# 1_0_-_First_design.net
KiCad netlist of a schematic drawn in EAGLE
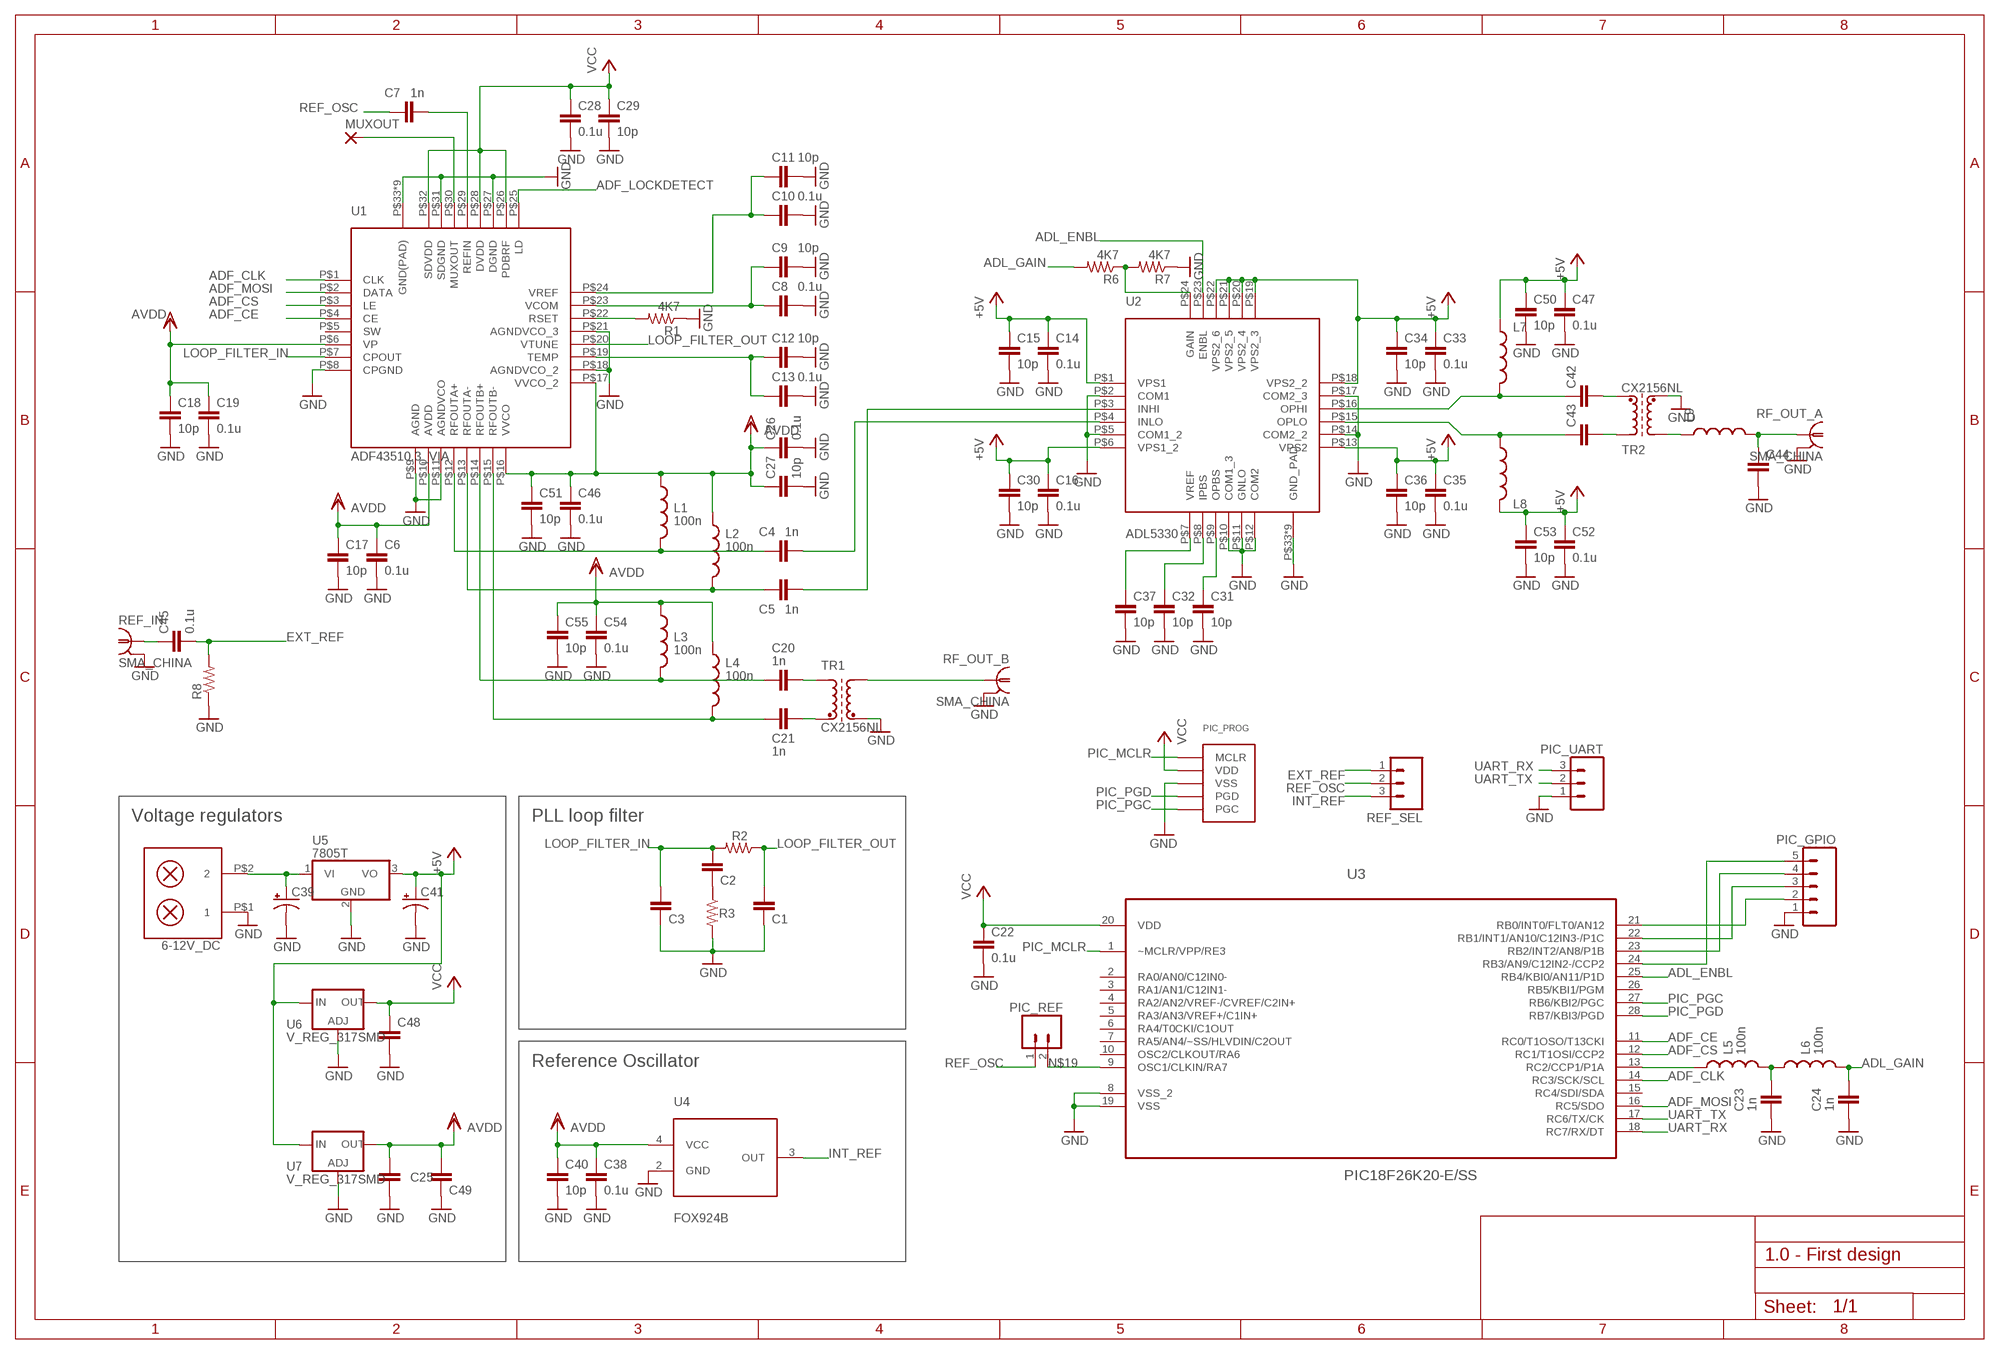
[diagram p0: schematic, sheet 1]

(export (version "E")
  (design (tool "Eeschema 10.0.6"))
  (components
    (comp (ref "6-12V_DC")
      (value "PK5602")
      (footprint "eagle-import:PK5602")
      (libsource (lib "eagle-import") (part "PK5602"))
    )
    (comp (ref "C1")
      (value "CAP0603-CAP")
      (footprint "eagle-import:0603-CAP")
      (libsource (lib "eagle-import") (part "CAP0603-CAP"))
    )
    (comp (ref "C2")
      (value "CAP0603-CAP")
      (footprint "eagle-import:0603-CAP")
      (libsource (lib "eagle-import") (part "CAP0603-CAP"))
    )
    (comp (ref "C3")
      (value "CAP0603-CAP")
      (footprint "eagle-import:0603-CAP")
      (libsource (lib "eagle-import") (part "CAP0603-CAP"))
    )
    (comp (ref "C4")
      (value "1n")
      (footprint "eagle-import:0603-CAP")
      (libsource (lib "eagle-import") (part "CAP0603-CAP"))
    )
    (comp (ref "C5")
      (value "1n")
      (footprint "eagle-import:0603-CAP")
      (libsource (lib "eagle-import") (part "CAP0603-CAP"))
    )
    (comp (ref "C6")
      (value "0.1u")
      (footprint "eagle-import:0603-CAP")
      (libsource (lib "eagle-import") (part "CAP0603-CAP"))
    )
    (comp (ref "C7")
      (value "1n")
      (footprint "eagle-import:0603-CAP")
      (libsource (lib "eagle-import") (part "CAP0603-CAP"))
    )
    (comp (ref "C8")
      (value "0.1u")
      (footprint "eagle-import:0603-CAP")
      (libsource (lib "eagle-import") (part "CAP0603-CAP"))
    )
    (comp (ref "C9")
      (value "10p")
      (footprint "eagle-import:0603-CAP")
      (libsource (lib "eagle-import") (part "CAP0603-CAP"))
    )
    (comp (ref "C10")
      (value "0.1u")
      (footprint "eagle-import:0603-CAP")
      (libsource (lib "eagle-import") (part "CAP0603-CAP"))
    )
    (comp (ref "C11")
      (value "10p")
      (footprint "eagle-import:0603-CAP")
      (libsource (lib "eagle-import") (part "CAP0603-CAP"))
    )
    (comp (ref "C12")
      (value "10p")
      (footprint "eagle-import:0603-CAP")
      (libsource (lib "eagle-import") (part "CAP0603-CAP"))
    )
    (comp (ref "C13")
      (value "0.1u")
      (footprint "eagle-import:0603-CAP")
      (libsource (lib "eagle-import") (part "CAP0603-CAP"))
    )
    (comp (ref "C14")
      (value "0.1u")
      (footprint "eagle-import:0603-CAP")
      (libsource (lib "eagle-import") (part "CAP0603-CAP"))
    )
    (comp (ref "C15")
      (value "10p")
      (footprint "eagle-import:0603-CAP")
      (libsource (lib "eagle-import") (part "CAP0603-CAP"))
    )
    (comp (ref "C16")
      (value "0.1u")
      (footprint "eagle-import:0603-CAP")
      (libsource (lib "eagle-import") (part "CAP0603-CAP"))
    )
    (comp (ref "C17")
      (value "10p")
      (footprint "eagle-import:0603-CAP")
      (libsource (lib "eagle-import") (part "CAP0603-CAP"))
    )
    (comp (ref "C18")
      (value "10p")
      (footprint "eagle-import:0603-CAP")
      (libsource (lib "eagle-import") (part "CAP0603-CAP"))
    )
    (comp (ref "C19")
      (value "0.1u")
      (footprint "eagle-import:0603-CAP")
      (libsource (lib "eagle-import") (part "CAP0603-CAP"))
    )
    (comp (ref "C20")
      (value "1n")
      (footprint "eagle-import:0603-CAP")
      (libsource (lib "eagle-import") (part "CAP0603-CAP"))
    )
    (comp (ref "C21")
      (value "1n")
      (footprint "eagle-import:0603-CAP")
      (libsource (lib "eagle-import") (part "CAP0603-CAP"))
    )
    (comp (ref "C22")
      (value "0.1u")
      (footprint "eagle-import:0603-CAP")
      (libsource (lib "eagle-import") (part "CAP0603-CAP"))
    )
    (comp (ref "C23")
      (value "1n")
      (footprint "eagle-import:0603-CAP")
      (libsource (lib "eagle-import") (part "CAP0603-CAP"))
    )
    (comp (ref "C24")
      (value "1n")
      (footprint "eagle-import:0603-CAP")
      (libsource (lib "eagle-import") (part "CAP0603-CAP"))
    )
    (comp (ref "C25")
      (value "C-EUC0805")
      (footprint "eagle-import:C0805")
      (libsource (lib "eagle-import") (part "C-EUC0805"))
    )
    (comp (ref "C26")
      (value "0.1u")
      (footprint "eagle-import:0603-CAP")
      (libsource (lib "eagle-import") (part "CAP0603-CAP"))
    )
    (comp (ref "C27")
      (value "10p")
      (footprint "eagle-import:0603-CAP")
      (libsource (lib "eagle-import") (part "CAP0603-CAP"))
    )
    (comp (ref "C28")
      (value "0.1u")
      (footprint "eagle-import:0603-CAP")
      (libsource (lib "eagle-import") (part "CAP0603-CAP"))
    )
    (comp (ref "C29")
      (value "10p")
      (footprint "eagle-import:0603-CAP")
      (libsource (lib "eagle-import") (part "CAP0603-CAP"))
    )
    (comp (ref "C30")
      (value "10p")
      (footprint "eagle-import:0603-CAP")
      (libsource (lib "eagle-import") (part "CAP0603-CAP"))
    )
    (comp (ref "C31")
      (value "10p")
      (footprint "eagle-import:0603-CAP")
      (libsource (lib "eagle-import") (part "CAP0603-CAP"))
    )
    (comp (ref "C32")
      (value "10p")
      (footprint "eagle-import:0603-CAP")
      (libsource (lib "eagle-import") (part "CAP0603-CAP"))
    )
    (comp (ref "C33")
      (value "0.1u")
      (footprint "eagle-import:0603-CAP")
      (libsource (lib "eagle-import") (part "CAP0603-CAP"))
    )
    (comp (ref "C34")
      (value "10p")
      (footprint "eagle-import:0603-CAP")
      (libsource (lib "eagle-import") (part "CAP0603-CAP"))
    )
    (comp (ref "C35")
      (value "0.1u")
      (footprint "eagle-import:0603-CAP")
      (libsource (lib "eagle-import") (part "CAP0603-CAP"))
    )
    (comp (ref "C36")
      (value "10p")
      (footprint "eagle-import:0603-CAP")
      (libsource (lib "eagle-import") (part "CAP0603-CAP"))
    )
    (comp (ref "C37")
      (value "10p")
      (footprint "eagle-import:0603-CAP")
      (libsource (lib "eagle-import") (part "CAP0603-CAP"))
    )
    (comp (ref "C38")
      (value "0.1u")
      (footprint "eagle-import:0603-CAP")
      (libsource (lib "eagle-import") (part "CAP0603-CAP"))
    )
    (comp (ref "C39")
      (value "CAP_POLSMD")
      (footprint "eagle-import:VISHAY_C")
      (libsource (lib "eagle-import") (part "CAP_POLSMD"))
    )
    (comp (ref "C40")
      (value "10p")
      (footprint "eagle-import:0603-CAP")
      (libsource (lib "eagle-import") (part "CAP0603-CAP"))
    )
    (comp (ref "C41")
      (value "CAP_POLSMD")
      (footprint "eagle-import:VISHAY_C")
      (libsource (lib "eagle-import") (part "CAP_POLSMD"))
    )
    (comp (ref "C42")
      (value "CAP")
      (footprint "eagle-import:C0805K")
      (libsource (lib "eagle-import") (part "CAP"))
    )
    (comp (ref "C43")
      (value "CAP")
      (footprint "eagle-import:C0805K")
      (libsource (lib "eagle-import") (part "CAP"))
    )
    (comp (ref "C44")
      (value "CAP")
      (footprint "eagle-import:C0805K")
      (libsource (lib "eagle-import") (part "CAP"))
    )
    (comp (ref "C45")
      (value "0.1u")
      (footprint "eagle-import:0603-CAP")
      (libsource (lib "eagle-import") (part "CAP0603-CAP"))
    )
    (comp (ref "C46")
      (value "0.1u")
      (footprint "eagle-import:0603-CAP")
      (libsource (lib "eagle-import") (part "CAP0603-CAP"))
    )
    (comp (ref "C47")
      (value "0.1u")
      (footprint "eagle-import:0603-CAP")
      (libsource (lib "eagle-import") (part "CAP0603-CAP"))
    )
    (comp (ref "C48")
      (value "C-EUC0805")
      (footprint "eagle-import:C0805")
      (libsource (lib "eagle-import") (part "C-EUC0805"))
    )
    (comp (ref "C49")
      (value "C-EUC0805")
      (footprint "eagle-import:C0805")
      (libsource (lib "eagle-import") (part "C-EUC0805"))
    )
    (comp (ref "C50")
      (value "10p")
      (footprint "eagle-import:0603-CAP")
      (libsource (lib "eagle-import") (part "CAP0603-CAP"))
    )
    (comp (ref "C51")
      (value "10p")
      (footprint "eagle-import:0603-CAP")
      (libsource (lib "eagle-import") (part "CAP0603-CAP"))
    )
    (comp (ref "C52")
      (value "0.1u")
      (footprint "eagle-import:0603-CAP")
      (libsource (lib "eagle-import") (part "CAP0603-CAP"))
    )
    (comp (ref "C53")
      (value "10p")
      (footprint "eagle-import:0603-CAP")
      (libsource (lib "eagle-import") (part "CAP0603-CAP"))
    )
    (comp (ref "C54")
      (value "0.1u")
      (footprint "eagle-import:0603-CAP")
      (libsource (lib "eagle-import") (part "CAP0603-CAP"))
    )
    (comp (ref "C55")
      (value "10p")
      (footprint "eagle-import:0603-CAP")
      (libsource (lib "eagle-import") (part "CAP0603-CAP"))
    )
    (comp (ref "L1")
      (value "100n")
      (footprint "eagle-import:0603")
      (libsource (lib "eagle-import") (part "INDUCTOR0603"))
    )
    (comp (ref "L2")
      (value "100n")
      (footprint "eagle-import:0603")
      (libsource (lib "eagle-import") (part "INDUCTOR0603"))
    )
    (comp (ref "L3")
      (value "100n")
      (footprint "eagle-import:0603")
      (libsource (lib "eagle-import") (part "INDUCTOR0603"))
    )
    (comp (ref "L4")
      (value "100n")
      (footprint "eagle-import:0603")
      (libsource (lib "eagle-import") (part "INDUCTOR0603"))
    )
    (comp (ref "L5")
      (value "100n")
      (footprint "eagle-import:0603")
      (libsource (lib "eagle-import") (part "INDUCTOR0603"))
    )
    (comp (ref "L6")
      (value "100n")
      (footprint "eagle-import:0603")
      (libsource (lib "eagle-import") (part "INDUCTOR0603"))
    )
    (comp (ref "L7")
      (value "INDUCTOR")
      (footprint "eagle-import:C0805K")
      (libsource (lib "eagle-import") (part "INDUCTOR"))
    )
    (comp (ref "L8")
      (value "INDUCTOR")
      (footprint "eagle-import:C0805K")
      (libsource (lib "eagle-import") (part "INDUCTOR"))
    )
    (comp (ref "L9")
      (value "INDUCTOR")
      (footprint "eagle-import:C0805K")
      (libsource (lib "eagle-import") (part "INDUCTOR"))
    )
    (comp (ref "MUXOUT")
      (value "SMD2")
      (footprint "eagle-import:SMD1,27-2,54")
      (libsource (lib "eagle-import") (part "SMD2"))
    )
    (comp (ref "PIC_GPIO")
      (value "M05PTH")
      (footprint "eagle-import:1X05")
      (libsource (lib "eagle-import") (part "M05PTH"))
    )
    (comp (ref "PIC_PROG")
      (value "1X5_ICSP")
      (footprint "eagle-import:1X5_2MM")
      (libsource (lib "eagle-import") (part "1X5_ICSP"))
    )
    (comp (ref "PIC_REF")
      (value "M02PTH")
      (footprint "eagle-import:1X02")
      (libsource (lib "eagle-import") (part "M02PTH"))
    )
    (comp (ref "PIC_UART")
      (value "M03PTH")
      (footprint "eagle-import:1X03")
      (libsource (lib "eagle-import") (part "M03PTH"))
    )
    (comp (ref "R1")
      (value "4K7")
      (footprint "eagle-import:0603-RES")
      (libsource (lib "eagle-import") (part "RESISTOR0603-RES"))
    )
    (comp (ref "R2")
      (value "RESISTOR0603-RES")
      (footprint "eagle-import:0603-RES")
      (libsource (lib "eagle-import") (part "RESISTOR0603-RES"))
    )
    (comp (ref "R3")
      (value "RESISTOR0603-RES")
      (footprint "eagle-import:0603-RES")
      (libsource (lib "eagle-import") (part "RESISTOR0603-RES"))
    )
    (comp (ref "R6")
      (value "4K7")
      (footprint "eagle-import:0603-RES")
      (libsource (lib "eagle-import") (part "RESISTOR0603-RES"))
    )
    (comp (ref "R7")
      (value "4K7")
      (footprint "eagle-import:0603-RES")
      (libsource (lib "eagle-import") (part "RESISTOR0603-RES"))
    )
    (comp (ref "R8")
      (value "RESISTOR")
      (footprint "eagle-import:C0805K")
      (libsource (lib "eagle-import") (part "RESISTOR"))
    )
    (comp (ref "REF_IN")
      (value "SMA_CHINA")
      (footprint "eagle-import:SMA-EDGE")
      (libsource (lib "eagle-import") (part "SMA_CHINA"))
    )
    (comp (ref "REF_SEL")
      (value "M03PTH")
      (footprint "eagle-import:1X03")
      (libsource (lib "eagle-import") (part "M03PTH"))
    )
    (comp (ref "RF_OUT_A")
      (value "SMA_CHINA")
      (footprint "eagle-import:SMA-EDGE")
      (libsource (lib "eagle-import") (part "SMA_CHINA"))
    )
    (comp (ref "RF_OUT_B")
      (value "SMA_CHINA")
      (footprint "eagle-import:SMA-EDGE")
      (libsource (lib "eagle-import") (part "SMA_CHINA"))
    )
    (comp (ref "TR1")
      (value "CX2156NL")
      (footprint "eagle-import:CX2156NL")
      (libsource (lib "eagle-import") (part "CX2156NL"))
    )
    (comp (ref "TR2")
      (value "CX2156NL")
      (footprint "eagle-import:CX2156NL")
      (libsource (lib "eagle-import") (part "CX2156NL"))
    )
    (comp (ref "U1")
      (value "ADF43510.3_VIA")
      (footprint "eagle-import:LFCSP_CP-32-2_.3VIA")
      (libsource (lib "eagle-import") (part "ADF43510.3_VIA"))
    )
    (comp (ref "U2")
      (value "ADL5330")
      (footprint "eagle-import:LFCSP_CP-24-2_.3VIA")
      (libsource (lib "eagle-import") (part "ADL5330"))
    )
    (comp (ref "U3")
      (value "PIC18F26K20-E/SS")
      (footprint "eagle-import:SOP65P780X200-28N")
      (libsource (lib "eagle-import") (part "PIC18F26K20-E/SS"))
    )
    (comp (ref "U4")
      (value "FOX924B")
      (footprint "eagle-import:FOX924B")
      (libsource (lib "eagle-import") (part "FOX924B"))
    )
    (comp (ref "U5")
      (value "7805T")
      (footprint "eagle-import:TO220H")
      (libsource (lib "eagle-import") (part "78T05"))
    )
    (comp (ref "U6")
      (value "V_REG_317SMD")
      (footprint "eagle-import:SOT223")
      (libsource (lib "eagle-import") (part "V_REG_317SMD"))
    )
    (comp (ref "U7")
      (value "V_REG_317SMD")
      (footprint "eagle-import:SOT223")
      (libsource (lib "eagle-import") (part "V_REG_317SMD"))
    )
  )
  (nets
    (net (code "1") (name "+5V") (class "Default")
      (node (ref "C14") (pin "1") (pinfunction "1_1") (pintype "passive"))
      (node (ref "C15") (pin "1") (pinfunction "1_1") (pintype "passive"))
      (node (ref "C16") (pin "1") (pinfunction "1_1") (pintype "passive"))
      (node (ref "C30") (pin "1") (pinfunction "1_1") (pintype "passive"))
      (node (ref "C33") (pin "1") (pinfunction "1_1") (pintype "passive"))
      (node (ref "C34") (pin "1") (pinfunction "1_1") (pintype "passive"))
      (node (ref "C35") (pin "1") (pinfunction "1_1") (pintype "passive"))
      (node (ref "C36") (pin "1") (pinfunction "1_1") (pintype "passive"))
      (node (ref "C41") (pin "+") (pinfunction "+_+") (pintype "passive"))
      (node (ref "C47") (pin "1") (pinfunction "1_1") (pintype "passive"))
      (node (ref "C50") (pin "1") (pinfunction "1_1") (pintype "passive"))
      (node (ref "C52") (pin "1") (pinfunction "1_1") (pintype "passive"))
      (node (ref "C53") (pin "1") (pinfunction "1_1") (pintype "passive"))
      (node (ref "L7") (pin "1") (pinfunction "1_1") (pintype "passive"))
      (node (ref "L8") (pin "1") (pinfunction "1_1") (pintype "passive"))
      (node (ref "U2") (pin "P$1") (pinfunction "VPS1_P$1") (pintype "bidirectional"))
      (node (ref "U2") (pin "P$13") (pinfunction "VPS2_P$13") (pintype "bidirectional"))
      (node (ref "U2") (pin "P$18") (pinfunction "VPS2_2_P$18") (pintype "bidirectional"))
      (node (ref "U2") (pin "P$19") (pinfunction "VPS2_3_P$19") (pintype "bidirectional"))
      (node (ref "U2") (pin "P$20") (pinfunction "VPS2_4_P$20") (pintype "bidirectional"))
      (node (ref "U2") (pin "P$21") (pinfunction "VPS2_5_P$21") (pintype "bidirectional"))
      (node (ref "U2") (pin "P$22") (pinfunction "VPS2_6_P$22") (pintype "bidirectional"))
      (node (ref "U2") (pin "P$6") (pinfunction "VPS1_2_P$6") (pintype "bidirectional"))
      (node (ref "U5") (pin "3") (pinfunction "VO_3") (pintype "passive"))
      (node (ref "U6") (pin "3") (pinfunction "IN_3") (pintype "input"))
      (node (ref "U7") (pin "3") (pinfunction "IN_3") (pintype "input"))
    )
    (net (code "2") (name "/ADF_CE") (class "Default")
      (node (ref "U1") (pin "P$4") (pinfunction "CE_P$4") (pintype "bidirectional"))
      (node (ref "U3") (pin "11") (pinfunction "RC0/T1OSO/T13CKI_11") (pintype "bidirectional"))
    )
    (net (code "3") (name "/ADF_CLK") (class "Default")
      (node (ref "U1") (pin "P$1") (pinfunction "CLK_P$1") (pintype "bidirectional"))
      (node (ref "U3") (pin "14") (pinfunction "RC3/SCK/SCL_14") (pintype "bidirectional"))
    )
    (net (code "4") (name "/ADF_CS") (class "Default")
      (node (ref "U1") (pin "P$3") (pinfunction "LE_P$3") (pintype "bidirectional"))
      (node (ref "U3") (pin "12") (pinfunction "RC1/T1OSI/CCP2_12") (pintype "bidirectional"))
    )
    (net (code "5") (name "/ADF_LOCKDETECT") (class "Default")
      (node (ref "U1") (pin "P$25") (pinfunction "LD_P$25") (pintype "bidirectional"))
    )
    (net (code "6") (name "/ADF_MOSI") (class "Default")
      (node (ref "U1") (pin "P$2") (pinfunction "DATA_P$2") (pintype "bidirectional"))
      (node (ref "U3") (pin "16") (pinfunction "RC5/SDO_16") (pintype "bidirectional"))
    )
    (net (code "7") (name "/ADL_ENBL") (class "Default")
      (node (ref "U2") (pin "P$23") (pinfunction "ENBL_P$23") (pintype "bidirectional"))
      (node (ref "U3") (pin "25") (pinfunction "RB4/KBI0/AN11/P1D_25") (pintype "bidirectional"))
    )
    (net (code "8") (name "/ADL_GAIN") (class "Default")
      (node (ref "C24") (pin "2") (pinfunction "2_2") (pintype "passive"))
      (node (ref "L6") (pin "2") (pinfunction "2_2") (pintype "passive"))
      (node (ref "R6") (pin "2") (pinfunction "2_2") (pintype "passive"))
    )
    (net (code "9") (name "/EXT_REF") (class "Default")
      (node (ref "C45") (pin "2") (pinfunction "2_2") (pintype "passive"))
      (node (ref "R8") (pin "2") (pinfunction "2_2") (pintype "passive"))
      (node (ref "REF_SEL") (pin "1") (pinfunction "1_1") (pintype "passive"))
    )
    (net (code "10") (name "/INT_REF") (class "Default")
      (node (ref "REF_SEL") (pin "3") (pinfunction "3_3") (pintype "passive"))
      (node (ref "U4") (pin "3") (pinfunction "OUT_3") (pintype "bidirectional"))
    )
    (net (code "11") (name "/LOOP_FILTER_IN") (class "Default")
      (node (ref "C2") (pin "1") (pinfunction "1_1") (pintype "passive"))
      (node (ref "C3") (pin "1") (pinfunction "1_1") (pintype "passive"))
      (node (ref "R2") (pin "2") (pinfunction "2_2") (pintype "passive"))
      (node (ref "U1") (pin "P$7") (pinfunction "CPOUT_P$7") (pintype "bidirectional"))
    )
    (net (code "12") (name "/LOOP_FILTER_OUT") (class "Default")
      (node (ref "C1") (pin "1") (pinfunction "1_1") (pintype "passive"))
      (node (ref "R2") (pin "1") (pinfunction "1_1") (pintype "passive"))
      (node (ref "U1") (pin "P$20") (pinfunction "VTUNE_P$20") (pintype "bidirectional"))
    )
    (net (code "13") (name "/N$19") (class "Default")
      (node (ref "PIC_REF") (pin "2") (pinfunction "2_2") (pintype "passive"))
      (node (ref "U3") (pin "9") (pinfunction "OSC1/CLKIN/RA7_9") (pintype "bidirectional"))
    )
    (net (code "14") (name "/PIC_MCLR") (class "Default")
      (node (ref "PIC_PROG") (pin "P$1") (pinfunction "MCLR_P$1") (pintype "bidirectional"))
      (node (ref "U3") (pin "1") (pinfunction "~{MCLR/VPP/RE3}_1") (pintype "input"))
    )
    (net (code "15") (name "/PIC_PGC") (class "Default")
      (node (ref "PIC_PROG") (pin "P$5") (pinfunction "PGC_P$5") (pintype "bidirectional"))
      (node (ref "U3") (pin "27") (pinfunction "RB6/KBI2/PGC_27") (pintype "bidirectional"))
    )
    (net (code "16") (name "/PIC_PGD") (class "Default")
      (node (ref "PIC_PROG") (pin "P$4") (pinfunction "PGD_P$4") (pintype "bidirectional"))
      (node (ref "U3") (pin "28") (pinfunction "RB7/KBI3/PGD_28") (pintype "bidirectional"))
    )
    (net (code "17") (name "/REF_OSC") (class "Default")
      (node (ref "C7") (pin "1") (pinfunction "1_1") (pintype "passive"))
      (node (ref "PIC_REF") (pin "1") (pinfunction "1_1") (pintype "passive"))
      (node (ref "REF_SEL") (pin "2") (pinfunction "2_2") (pintype "passive"))
    )
    (net (code "18") (name "/UART_RX") (class "Default")
      (node (ref "PIC_UART") (pin "3") (pinfunction "3_3") (pintype "passive"))
      (node (ref "U3") (pin "18") (pinfunction "RC7/RX/DT_18") (pintype "bidirectional"))
    )
    (net (code "19") (name "/UART_TX") (class "Default")
      (node (ref "PIC_UART") (pin "2") (pinfunction "2_2") (pintype "passive"))
      (node (ref "U3") (pin "17") (pinfunction "RC6/TX/CK_17") (pintype "bidirectional"))
    )
    (net (code "20") (name "AVDD") (class "Default")
      (node (ref "C17") (pin "1") (pinfunction "1_1") (pintype "passive"))
      (node (ref "C18") (pin "1") (pinfunction "1_1") (pintype "passive"))
      (node (ref "C19") (pin "1") (pinfunction "1_1") (pintype "passive"))
      (node (ref "C25") (pin "1") (pinfunction "1_1") (pintype "passive"))
      (node (ref "C26") (pin "1") (pinfunction "1_1") (pintype "passive"))
      (node (ref "C27") (pin "1") (pinfunction "1_1") (pintype "passive"))
      (node (ref "C38") (pin "1") (pinfunction "1_1") (pintype "passive"))
      (node (ref "C40") (pin "1") (pinfunction "1_1") (pintype "passive"))
      (node (ref "C46") (pin "1") (pinfunction "1_1") (pintype "passive"))
      (node (ref "C49") (pin "1") (pinfunction "1_1") (pintype "passive"))
      (node (ref "C51") (pin "1") (pinfunction "1_1") (pintype "passive"))
      (node (ref "C54") (pin "1") (pinfunction "1_1") (pintype "passive"))
      (node (ref "C55") (pin "1") (pinfunction "1_1") (pintype "passive"))
      (node (ref "C6") (pin "1") (pinfunction "1_1") (pintype "passive"))
      (node (ref "L1") (pin "1") (pinfunction "1_1") (pintype "passive"))
      (node (ref "L2") (pin "1") (pinfunction "1_1") (pintype "passive"))
      (node (ref "L3") (pin "1") (pinfunction "1_1") (pintype "passive"))
      (node (ref "L4") (pin "1") (pinfunction "1_1") (pintype "passive"))
      (node (ref "U1") (pin "P$10") (pinfunction "AVDD_P$10") (pintype "bidirectional"))
      (node (ref "U1") (pin "P$16") (pinfunction "VVCO_P$16") (pintype "bidirectional"))
      (node (ref "U1") (pin "P$17") (pinfunction "VVCO_2_P$17") (pintype "bidirectional"))
      (node (ref "U1") (pin "P$6") (pinfunction "VP_P$6") (pintype "bidirectional"))
      (node (ref "U4") (pin "4") (pinfunction "VCC_4") (pintype "bidirectional"))
      (node (ref "U7") (pin "2") (pinfunction "OUT_2") (pintype "output"))
    )
    (net (code "21") (name "GND") (class "Default")
      (node (ref "6-12V_DC") (pin "P$1") (pinfunction "1_P$1") (pintype "bidirectional"))
      (node (ref "C1") (pin "2") (pinfunction "2_2") (pintype "passive"))
      (node (ref "C10") (pin "2") (pinfunction "2_2") (pintype "passive"))
      (node (ref "C11") (pin "2") (pinfunction "2_2") (pintype "passive"))
      (node (ref "C12") (pin "2") (pinfunction "2_2") (pintype "passive"))
      (node (ref "C13") (pin "2") (pinfunction "2_2") (pintype "passive"))
      (node (ref "C14") (pin "2") (pinfunction "2_2") (pintype "passive"))
      (node (ref "C15") (pin "2") (pinfunction "2_2") (pintype "passive"))
      (node (ref "C16") (pin "2") (pinfunction "2_2") (pintype "passive"))
      (node (ref "C17") (pin "2") (pinfunction "2_2") (pintype "passive"))
      (node (ref "C18") (pin "2") (pinfunction "2_2") (pintype "passive"))
      (node (ref "C19") (pin "2") (pinfunction "2_2") (pintype "passive"))
      (node (ref "C22") (pin "2") (pinfunction "2_2") (pintype "passive"))
      (node (ref "C23") (pin "1") (pinfunction "1_1") (pintype "passive"))
      (node (ref "C24") (pin "1") (pinfunction "1_1") (pintype "passive"))
      (node (ref "C25") (pin "2") (pinfunction "2_2") (pintype "passive"))
      (node (ref "C26") (pin "2") (pinfunction "2_2") (pintype "passive"))
      (node (ref "C27") (pin "2") (pinfunction "2_2") (pintype "passive"))
      (node (ref "C28") (pin "2") (pinfunction "2_2") (pintype "passive"))
      (node (ref "C29") (pin "2") (pinfunction "2_2") (pintype "passive"))
      (node (ref "C3") (pin "2") (pinfunction "2_2") (pintype "passive"))
      (node (ref "C30") (pin "2") (pinfunction "2_2") (pintype "passive"))
      (node (ref "C31") (pin "2") (pinfunction "2_2") (pintype "passive"))
      (node (ref "C32") (pin "2") (pinfunction "2_2") (pintype "passive"))
      (node (ref "C33") (pin "2") (pinfunction "2_2") (pintype "passive"))
      (node (ref "C34") (pin "2") (pinfunction "2_2") (pintype "passive"))
      (node (ref "C35") (pin "2") (pinfunction "2_2") (pintype "passive"))
      (node (ref "C36") (pin "2") (pinfunction "2_2") (pintype "passive"))
      (node (ref "C37") (pin "2") (pinfunction "2_2") (pintype "passive"))
      (node (ref "C38") (pin "2") (pinfunction "2_2") (pintype "passive"))
      (node (ref "C39") (pin "-") (pinfunction "-_-") (pintype "passive"))
      (node (ref "C40") (pin "2") (pinfunction "2_2") (pintype "passive"))
      (node (ref "C41") (pin "-") (pinfunction "-_-") (pintype "passive"))
      (node (ref "C44") (pin "2") (pinfunction "2_2") (pintype "passive"))
      (node (ref "C46") (pin "2") (pinfunction "2_2") (pintype "passive"))
      (node (ref "C47") (pin "2") (pinfunction "2_2") (pintype "passive"))
      (node (ref "C48") (pin "2") (pinfunction "2_2") (pintype "passive"))
      (node (ref "C49") (pin "2") (pinfunction "2_2") (pintype "passive"))
      (node (ref "C50") (pin "2") (pinfunction "2_2") (pintype "passive"))
      (node (ref "C51") (pin "2") (pinfunction "2_2") (pintype "passive"))
      (node (ref "C52") (pin "2") (pinfunction "2_2") (pintype "passive"))
      (node (ref "C53") (pin "2") (pinfunction "2_2") (pintype "passive"))
      (node (ref "C54") (pin "2") (pinfunction "2_2") (pintype "passive"))
      (node (ref "C55") (pin "2") (pinfunction "2_2") (pintype "passive"))
      (node (ref "C6") (pin "2") (pinfunction "2_2") (pintype "passive"))
      (node (ref "C8") (pin "2") (pinfunction "2_2") (pintype "passive"))
      (node (ref "C9") (pin "2") (pinfunction "2_2") (pintype "passive"))
      (node (ref "PIC_GPIO") (pin "1") (pinfunction "1_1") (pintype "passive"))
      (node (ref "PIC_PROG") (pin "P$3") (pinfunction "VSS_P$3") (pintype "power_in"))
      (node (ref "PIC_UART") (pin "1") (pinfunction "1_1") (pintype "passive"))
      (node (ref "R1") (pin "1") (pinfunction "1_1") (pintype "passive"))
      (node (ref "R3") (pin "2") (pinfunction "2_2") (pintype "passive"))
      (node (ref "R7") (pin "1") (pinfunction "1_1") (pintype "passive"))
      (node (ref "R8") (pin "1") (pinfunction "1_1") (pintype "passive"))
      (node (ref "REF_IN") (pin "GND@0") (pinfunction "GND_GND@0") (pintype "power_in"))
      (node (ref "REF_IN") (pin "GND@1") (pinfunction "GND_GND@1") (pintype "power_in"))
      (node (ref "REF_IN") (pin "GND@2") (pinfunction "GND_GND@2") (pintype "power_in"))
      (node (ref "REF_IN") (pin "GND@3") (pinfunction "GND_GND@3") (pintype "power_in"))
      (node (ref "RF_OUT_A") (pin "GND@0") (pinfunction "GND_GND@0") (pintype "power_in"))
      (node (ref "RF_OUT_A") (pin "GND@1") (pinfunction "GND_GND@1") (pintype "power_in"))
      (node (ref "RF_OUT_A") (pin "GND@2") (pinfunction "GND_GND@2") (pintype "power_in"))
      (node (ref "RF_OUT_A") (pin "GND@3") (pinfunction "GND_GND@3") (pintype "power_in"))
      (node (ref "RF_OUT_B") (pin "GND@0") (pinfunction "GND_GND@0") (pintype "power_in"))
      (node (ref "RF_OUT_B") (pin "GND@1") (pinfunction "GND_GND@1") (pintype "power_in"))
      (node (ref "RF_OUT_B") (pin "GND@2") (pinfunction "GND_GND@2") (pintype "power_in"))
      (node (ref "RF_OUT_B") (pin "GND@3") (pinfunction "GND_GND@3") (pintype "power_in"))
      (node (ref "TR1") (pin "5") (pinfunction "E2_5") (pintype "passive"))
      (node (ref "TR2") (pin "5") (pinfunction "E2_5") (pintype "passive"))
      (node (ref "U1") (pin "P$11") (pinfunction "AGNDVCO_P$11") (pintype "bidirectional"))
      (node (ref "U1") (pin "P$18") (pinfunction "AGNDVCO_2_P$18") (pintype "bidirectional"))
      (node (ref "U1") (pin "P$21") (pinfunction "AGNDVCO_3_P$21") (pintype "bidirectional"))
      (node (ref "U1") (pin "P$27") (pinfunction "DGND_P$27") (pintype "bidirectional"))
      (node (ref "U1") (pin "P$31") (pinfunction "SDGND_P$31") (pintype "bidirectional"))
      (node (ref "U1") (pin "P$33") (pinfunction "GND(PAD)_P$33") (pintype "bidirectional"))
      (node (ref "U1") (pin "P$34") (pinfunction "GND(PAD)_P$34") (pintype "bidirectional"))
      (node (ref "U1") (pin "P$35") (pinfunction "GND(PAD)_P$35") (pintype "bidirectional"))
      (node (ref "U1") (pin "P$36") (pinfunction "GND(PAD)_P$36") (pintype "bidirectional"))
      (node (ref "U1") (pin "P$37") (pinfunction "GND(PAD)_P$37") (pintype "bidirectional"))
      (node (ref "U1") (pin "P$38") (pinfunction "GND(PAD)_P$38") (pintype "bidirectional"))
      (node (ref "U1") (pin "P$39") (pinfunction "GND(PAD)_P$39") (pintype "bidirectional"))
      (node (ref "U1") (pin "P$40") (pinfunction "GND(PAD)_P$40") (pintype "bidirectional"))
      (node (ref "U1") (pin "P$41") (pinfunction "GND(PAD)_P$41") (pintype "bidirectional"))
      (node (ref "U1") (pin "P$8") (pinfunction "CPGND_P$8") (pintype "bidirectional"))
      (node (ref "U1") (pin "P$9") (pinfunction "AGND_P$9") (pintype "bidirectional"))
      (node (ref "U2") (pin "P$10") (pinfunction "COM1_3_P$10") (pintype "bidirectional"))
      (node (ref "U2") (pin "P$11") (pinfunction "GNLO_P$11") (pintype "bidirectional"))
      (node (ref "U2") (pin "P$12") (pinfunction "COM2_P$12") (pintype "bidirectional"))
      (node (ref "U2") (pin "P$14") (pinfunction "COM2_2_P$14") (pintype "bidirectional"))
      (node (ref "U2") (pin "P$17") (pinfunction "COM2_3_P$17") (pintype "bidirectional"))
      (node (ref "U2") (pin "P$2") (pinfunction "COM1_P$2") (pintype "bidirectional"))
      (node (ref "U2") (pin "P$33") (pinfunction "GND_PAD_P$33") (pintype "bidirectional"))
      (node (ref "U2") (pin "P$34") (pinfunction "GND_PAD_P$34") (pintype "bidirectional"))
      (node (ref "U2") (pin "P$35") (pinfunction "GND_PAD_P$35") (pintype "bidirectional"))
      (node (ref "U2") (pin "P$36") (pinfunction "GND_PAD_P$36") (pintype "bidirectional"))
      (node (ref "U2") (pin "P$37") (pinfunction "GND_PAD_P$37") (pintype "bidirectional"))
      (node (ref "U2") (pin "P$38") (pinfunction "GND_PAD_P$38") (pintype "bidirectional"))
      (node (ref "U2") (pin "P$39") (pinfunction "GND_PAD_P$39") (pintype "bidirectional"))
      (node (ref "U2") (pin "P$40") (pinfunction "GND_PAD_P$40") (pintype "bidirectional"))
      (node (ref "U2") (pin "P$41") (pinfunction "GND_PAD_P$41") (pintype "bidirectional"))
      (node (ref "U2") (pin "P$5") (pinfunction "COM1_2_P$5") (pintype "bidirectional"))
      (node (ref "U3") (pin "19") (pinfunction "VSS_19") (pintype "power_in"))
      (node (ref "U3") (pin "8") (pinfunction "VSS_2_8") (pintype "power_in"))
      (node (ref "U4") (pin "2") (pinfunction "GND_2") (pintype "bidirectional"))
      (node (ref "U5") (pin "2") (pinfunction "GND_2") (pintype "passive"))
      (node (ref "U6") (pin "1") (pinfunction "ADJ_1") (pintype "input"))
      (node (ref "U7") (pin "1") (pinfunction "ADJ_1") (pintype "input"))
    )
    (net (code "22") (name "Net-(6-12V_DC-2)") (class "Default")
      (node (ref "6-12V_DC") (pin "P$2") (pinfunction "2_P$2") (pintype "bidirectional"))
      (node (ref "C39") (pin "+") (pinfunction "+_+") (pintype "passive"))
      (node (ref "U5") (pin "1") (pinfunction "VI_1") (pintype "input"))
    )
    (net (code "23") (name "Net-(C2-Pad2)") (class "Default")
      (node (ref "C2") (pin "2") (pinfunction "2_2") (pintype "passive"))
      (node (ref "R3") (pin "1") (pinfunction "1_1") (pintype "passive"))
    )
    (net (code "24") (name "Net-(C23-Pad2)") (class "Default")
      (node (ref "C23") (pin "2") (pinfunction "2_2") (pintype "passive"))
      (node (ref "L5") (pin "2") (pinfunction "2_2") (pintype "passive"))
      (node (ref "L6") (pin "1") (pinfunction "1_1") (pintype "passive"))
    )
    (net (code "25") (name "Net-(MUXOUT-P)") (class "Default")
      (node (ref "MUXOUT") (pin "1") (pinfunction "P_1") (pintype "passive"))
      (node (ref "U1") (pin "P$30") (pinfunction "MUXOUT_P$30") (pintype "bidirectional"))
    )
    (net (code "26") (name "Net-(REF_IN-1)") (class "Default")
      (node (ref "C45") (pin "1") (pinfunction "1_1") (pintype "passive"))
      (node (ref "REF_IN") (pin "SIG") (pinfunction "1_SIG") (pintype "passive"))
    )
    (net (code "27") (name "Net-(RF_OUT_A-1)") (class "Default")
      (node (ref "C44") (pin "1") (pinfunction "1_1") (pintype "passive"))
      (node (ref "L9") (pin "2") (pinfunction "2_2") (pintype "passive"))
      (node (ref "RF_OUT_A") (pin "SIG") (pinfunction "1_SIG") (pintype "passive"))
    )
    (net (code "28") (name "Net-(RF_OUT_B-1)") (class "Default")
      (node (ref "RF_OUT_B") (pin "SIG") (pinfunction "1_SIG") (pintype "passive"))
      (node (ref "TR1") (pin "4") (pinfunction "A2_4") (pintype "passive"))
    )
    (net (code "29") (name "Net-(TR1-A1)") (class "Default")
      (node (ref "C20") (pin "2") (pinfunction "2_2") (pintype "passive"))
      (node (ref "TR1") (pin "3") (pinfunction "A1_3") (pintype "passive"))
    )
    (net (code "30") (name "Net-(TR1-E1)") (class "Default")
      (node (ref "C21") (pin "2") (pinfunction "2_2") (pintype "passive"))
      (node (ref "TR1") (pin "1") (pinfunction "E1_1") (pintype "passive"))
    )
    (net (code "31") (name "Net-(TR2-A1)") (class "Default")
      (node (ref "C43") (pin "2") (pinfunction "2_2") (pintype "passive"))
      (node (ref "TR2") (pin "3") (pinfunction "A1_3") (pintype "passive"))
    )
    (net (code "32") (name "Net-(TR2-A2)") (class "Default")
      (node (ref "L9") (pin "1") (pinfunction "1_1") (pintype "passive"))
      (node (ref "TR2") (pin "4") (pinfunction "A2_4") (pintype "passive"))
    )
    (net (code "33") (name "Net-(TR2-E1)") (class "Default")
      (node (ref "C42") (pin "2") (pinfunction "2_2") (pintype "passive"))
      (node (ref "TR2") (pin "1") (pinfunction "E1_1") (pintype "passive"))
    )
    (net (code "34") (name "Net-(U1-REFIN)") (class "Default")
      (node (ref "C7") (pin "2") (pinfunction "2_2") (pintype "passive"))
      (node (ref "U1") (pin "P$29") (pinfunction "REFIN_P$29") (pintype "bidirectional"))
    )
    (net (code "35") (name "Net-(U1-RFOUTA+)") (class "Default")
      (node (ref "C4") (pin "1") (pinfunction "1_1") (pintype "passive"))
      (node (ref "L1") (pin "2") (pinfunction "2_2") (pintype "passive"))
      (node (ref "U1") (pin "P$12") (pinfunction "RFOUTA+_P$12") (pintype "bidirectional"))
    )
    (net (code "36") (name "Net-(U1-RFOUTA-)") (class "Default")
      (node (ref "C5") (pin "1") (pinfunction "1_1") (pintype "passive"))
      (node (ref "L2") (pin "2") (pinfunction "2_2") (pintype "passive"))
      (node (ref "U1") (pin "P$13") (pinfunction "RFOUTA-_P$13") (pintype "bidirectional"))
    )
    (net (code "37") (name "Net-(U1-RFOUTB+)") (class "Default")
      (node (ref "C20") (pin "1") (pinfunction "1_1") (pintype "passive"))
      (node (ref "L3") (pin "2") (pinfunction "2_2") (pintype "passive"))
      (node (ref "U1") (pin "P$14") (pinfunction "RFOUTB+_P$14") (pintype "bidirectional"))
    )
    (net (code "38") (name "Net-(U1-RFOUTB-)") (class "Default")
      (node (ref "C21") (pin "1") (pinfunction "1_1") (pintype "passive"))
      (node (ref "L4") (pin "2") (pinfunction "2_2") (pintype "passive"))
      (node (ref "U1") (pin "P$15") (pinfunction "RFOUTB-_P$15") (pintype "bidirectional"))
    )
    (net (code "39") (name "Net-(U1-RSET)") (class "Default")
      (node (ref "R1") (pin "2") (pinfunction "2_2") (pintype "passive"))
      (node (ref "U1") (pin "P$22") (pinfunction "RSET_P$22") (pintype "bidirectional"))
    )
    (net (code "40") (name "Net-(U1-TEMP)") (class "Default")
      (node (ref "C12") (pin "1") (pinfunction "1_1") (pintype "passive"))
      (node (ref "C13") (pin "1") (pinfunction "1_1") (pintype "passive"))
      (node (ref "U1") (pin "P$19") (pinfunction "TEMP_P$19") (pintype "bidirectional"))
    )
    (net (code "41") (name "Net-(U1-VCOM)") (class "Default")
      (node (ref "C8") (pin "1") (pinfunction "1_1") (pintype "passive"))
      (node (ref "C9") (pin "1") (pinfunction "1_1") (pintype "passive"))
      (node (ref "U1") (pin "P$23") (pinfunction "VCOM_P$23") (pintype "bidirectional"))
    )
    (net (code "42") (name "Net-(U1-VREF)") (class "Default")
      (node (ref "C10") (pin "1") (pinfunction "1_1") (pintype "passive"))
      (node (ref "C11") (pin "1") (pinfunction "1_1") (pintype "passive"))
      (node (ref "U1") (pin "P$24") (pinfunction "VREF_P$24") (pintype "bidirectional"))
    )
    (net (code "43") (name "Net-(U2-GAIN)") (class "Default")
      (node (ref "R6") (pin "1") (pinfunction "1_1") (pintype "passive"))
      (node (ref "R7") (pin "2") (pinfunction "2_2") (pintype "passive"))
      (node (ref "U2") (pin "P$24") (pinfunction "GAIN_P$24") (pintype "bidirectional"))
    )
    (net (code "44") (name "Net-(U2-INHI)") (class "Default")
      (node (ref "C5") (pin "2") (pinfunction "2_2") (pintype "passive"))
      (node (ref "U2") (pin "P$3") (pinfunction "INHI_P$3") (pintype "bidirectional"))
    )
    (net (code "45") (name "Net-(U2-INLO)") (class "Default")
      (node (ref "C4") (pin "2") (pinfunction "2_2") (pintype "passive"))
      (node (ref "U2") (pin "P$4") (pinfunction "INLO_P$4") (pintype "bidirectional"))
    )
    (net (code "46") (name "Net-(U2-IPBS)") (class "Default")
      (node (ref "C32") (pin "1") (pinfunction "1_1") (pintype "passive"))
      (node (ref "U2") (pin "P$8") (pinfunction "IPBS_P$8") (pintype "bidirectional"))
    )
    (net (code "47") (name "Net-(U2-OPBS)") (class "Default")
      (node (ref "C31") (pin "1") (pinfunction "1_1") (pintype "passive"))
      (node (ref "U2") (pin "P$9") (pinfunction "OPBS_P$9") (pintype "bidirectional"))
    )
    (net (code "48") (name "Net-(U2-OPHI)") (class "Default")
      (node (ref "C42") (pin "1") (pinfunction "1_1") (pintype "passive"))
      (node (ref "L7") (pin "2") (pinfunction "2_2") (pintype "passive"))
      (node (ref "U2") (pin "P$16") (pinfunction "OPHI_P$16") (pintype "bidirectional"))
    )
    (net (code "49") (name "Net-(U2-OPLO)") (class "Default")
      (node (ref "C43") (pin "1") (pinfunction "1_1") (pintype "passive"))
      (node (ref "L8") (pin "2") (pinfunction "2_2") (pintype "passive"))
      (node (ref "U2") (pin "P$15") (pinfunction "OPLO_P$15") (pintype "bidirectional"))
    )
    (net (code "50") (name "Net-(U2-VREF)") (class "Default")
      (node (ref "C37") (pin "1") (pinfunction "1_1") (pintype "passive"))
      (node (ref "U2") (pin "P$7") (pinfunction "VREF_P$7") (pintype "bidirectional"))
    )
    (net (code "51") (name "Net-(U3-RB0{slash}INT0{slash}FLT0{slash}AN12)") (class "Default")
      (node (ref "PIC_GPIO") (pin "2") (pinfunction "2_2") (pintype "passive"))
      (node (ref "U3") (pin "21") (pinfunction "RB0/INT0/FLT0/AN12_21") (pintype "bidirectional"))
    )
    (net (code "52") (name "Net-(U3-RB1{slash}INT1{slash}AN10{slash}C12IN3-{slash}P1C)") (class "Default")
      (node (ref "PIC_GPIO") (pin "3") (pinfunction "3_3") (pintype "passive"))
      (node (ref "U3") (pin "22") (pinfunction "RB1/INT1/AN10/C12IN3-/P1C_22") (pintype "bidirectional"))
    )
    (net (code "53") (name "Net-(U3-RB2{slash}INT2{slash}AN8{slash}P1B)") (class "Default")
      (node (ref "PIC_GPIO") (pin "4") (pinfunction "4_4") (pintype "passive"))
      (node (ref "U3") (pin "23") (pinfunction "RB2/INT2/AN8/P1B_23") (pintype "bidirectional"))
    )
    (net (code "54") (name "Net-(U3-RB3{slash}AN9{slash}C12IN2-{slash}CCP2)") (class "Default")
      (node (ref "PIC_GPIO") (pin "5") (pinfunction "5_5") (pintype "passive"))
      (node (ref "U3") (pin "24") (pinfunction "RB3/AN9/C12IN2-/CCP2_24") (pintype "bidirectional"))
    )
    (net (code "55") (name "Net-(U3-RC2{slash}CCP1{slash}P1A)") (class "Default")
      (node (ref "L5") (pin "1") (pinfunction "1_1") (pintype "passive"))
      (node (ref "U3") (pin "13") (pinfunction "RC2/CCP1/P1A_13") (pintype "bidirectional"))
    )
    (net (code "56") (name "VCC") (class "Default")
      (node (ref "C22") (pin "1") (pinfunction "1_1") (pintype "passive"))
      (node (ref "C28") (pin "1") (pinfunction "1_1") (pintype "passive"))
      (node (ref "C29") (pin "1") (pinfunction "1_1") (pintype "passive"))
      (node (ref "C48") (pin "1") (pinfunction "1_1") (pintype "passive"))
      (node (ref "PIC_PROG") (pin "P$2") (pinfunction "VDD_P$2") (pintype "power_in"))
      (node (ref "U1") (pin "P$26") (pinfunction "PDBRF_P$26") (pintype "bidirectional"))
      (node (ref "U1") (pin "P$28") (pinfunction "DVDD_P$28") (pintype "bidirectional"))
      (node (ref "U1") (pin "P$32") (pinfunction "SDVDD_P$32") (pintype "bidirectional"))
      (node (ref "U3") (pin "20") (pinfunction "VDD_20") (pintype "power_in"))
      (node (ref "U6") (pin "2") (pinfunction "OUT_2") (pintype "output"))
    )
    (net (code "57") (name "unconnected-(U1-SW-PadP$5)") (class "Default")
      (node (ref "U1") (pin "P$5") (pinfunction "SW_P$5") (pintype "bidirectional"))
    )
    (net (code "58") (name "unconnected-(U3-OSC2{slash}CLKOUT{slash}RA6-Pad10)") (class "Default")
      (node (ref "U3") (pin "10") (pinfunction "OSC2/CLKOUT/RA6_10") (pintype "bidirectional"))
    )
    (net (code "59") (name "unconnected-(U3-RA0{slash}AN0{slash}C12IN0--Pad2)") (class "Default")
      (node (ref "U3") (pin "2") (pinfunction "RA0/AN0/C12IN0-_2") (pintype "bidirectional"))
    )
    (net (code "60") (name "unconnected-(U3-RA1{slash}AN1{slash}C12IN1--Pad3)") (class "Default")
      (node (ref "U3") (pin "3") (pinfunction "RA1/AN1/C12IN1-_3") (pintype "bidirectional"))
    )
    (net (code "61") (name "unconnected-(U3-RA2{slash}AN2{slash}VREF-{slash}CVREF{slash}C2IN+-Pad4)") (class "Default")
      (node (ref "U3") (pin "4") (pinfunction "RA2/AN2/VREF-/CVREF/C2IN+_4") (pintype "bidirectional"))
    )
    (net (code "62") (name "unconnected-(U3-RA3{slash}AN3{slash}VREF+{slash}C1IN+-Pad5)") (class "Default")
      (node (ref "U3") (pin "5") (pinfunction "RA3/AN3/VREF+/C1IN+_5") (pintype "bidirectional"))
    )
    (net (code "63") (name "unconnected-(U3-RA4{slash}T0CKI{slash}C1OUT-Pad6)") (class "Default")
      (node (ref "U3") (pin "6") (pinfunction "RA4/T0CKI/C1OUT_6") (pintype "bidirectional"))
    )
    (net (code "64") (name "unconnected-(U3-RA5{slash}AN4{slash}~{SS{slash}HLVDIN{slash}C2OUT}-Pad7)") (class "Default")
      (node (ref "U3") (pin "7") (pinfunction "RA5/AN4/~{SS/HLVDIN/C2OUT}_7") (pintype "bidirectional"))
    )
    (net (code "65") (name "unconnected-(U3-RB5{slash}KBI1{slash}PGM-Pad26)") (class "Default")
      (node (ref "U3") (pin "26") (pinfunction "RB5/KBI1/PGM_26") (pintype "bidirectional"))
    )
    (net (code "66") (name "unconnected-(U3-RC4{slash}SDI{slash}SDA-Pad15)") (class "Default")
      (node (ref "U3") (pin "15") (pinfunction "RC4/SDI/SDA_15") (pintype "bidirectional"))
    )
  )
)
